# Crystal_Reset_Boot.net
KiCad netlist of a schematic drawn in Altium Designer
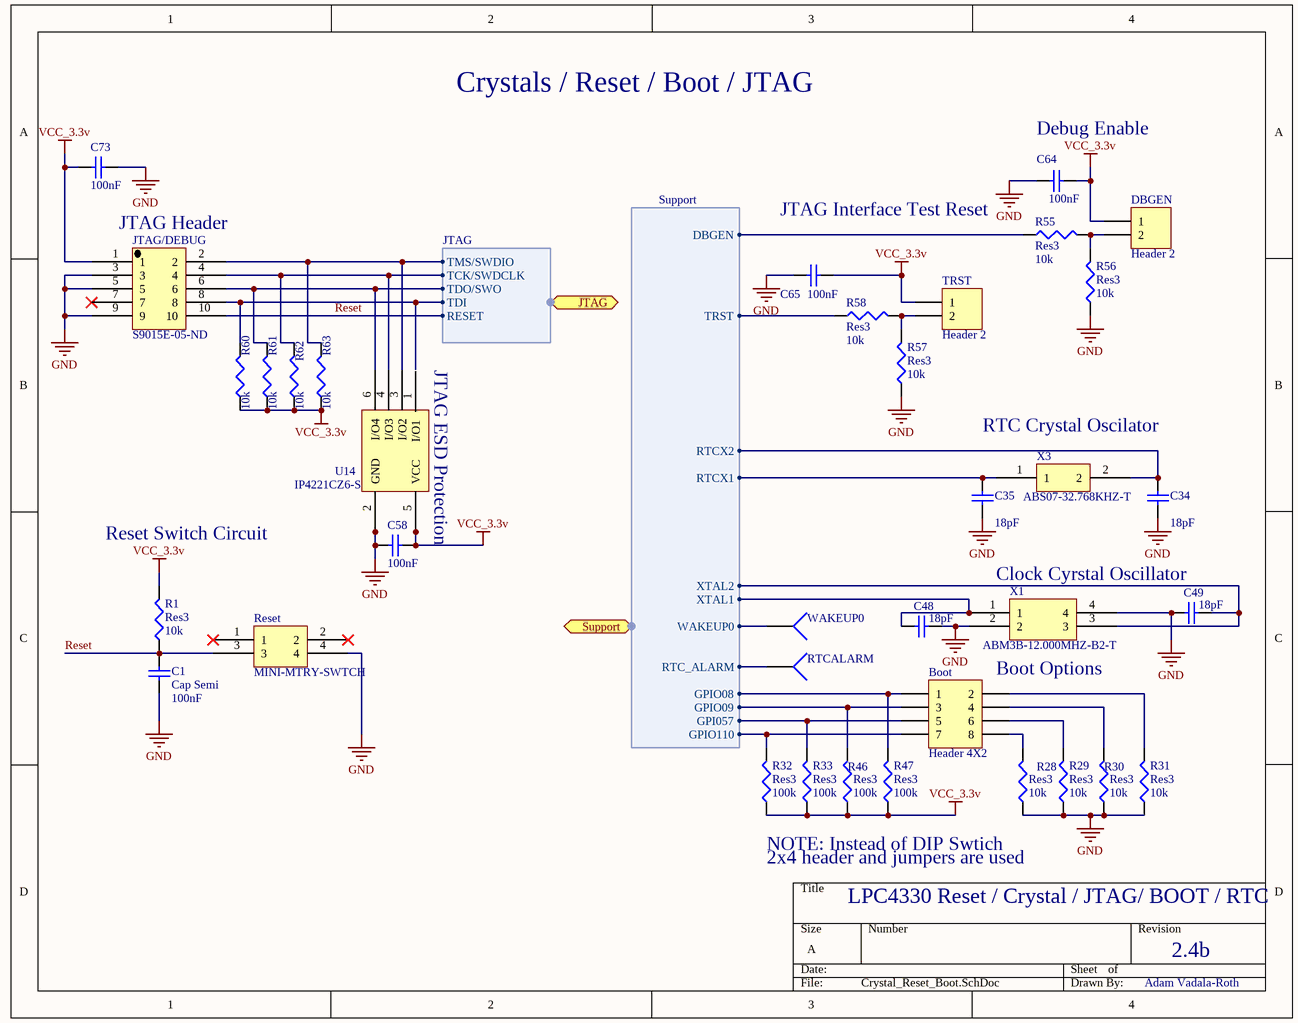
[diagram p0: Crystal_Reset_Boot.SchDoc]

(export (version "E")
  (design (tool "Eeschema 10.0.6"))
  (components
    (comp (ref "Boot")
      (value "Header 4X2")
      (footprint "HDR2X4")
      (description "Header, 4-Pin, Dual row")
      (fields (field (name "PUBLISHER") "Altium Limited"))
      (libsource (lib "Miscellaneous Connectors") (part "Header 4X2"))
    )
    (comp (ref "C1")
      (value "Cap Semi")
      (footprint "CAPC1608L")
      (description "Capacitor (Semiconductor SIM Model)")
      (fields (field (name "C1") "100nF") (field (name "PUBLISHER") "Altium Limited"))
      (libsource (lib "Miscellaneous Devices") (part "Cap Semi"))
    )
    (comp (ref "C34")
      (value "18pF")
      (footprint "1608[0603]")
      (description "Capacitor (Semiconductor SIM Model)")
      (fields (field (name "Comment") "Cap Semi") (field (name "PUBLISHER") "Altium Limited"))
      (libsource (lib "Miscellaneous Devices") (part "Cap Semi"))
    )
    (comp (ref "C35")
      (value "18pF")
      (footprint "1608[0603]")
      (description "Capacitor (Semiconductor SIM Model)")
      (fields (field (name "Comment") "Cap Semi") (field (name "PUBLISHER") "Altium Limited"))
      (libsource (lib "Miscellaneous Devices") (part "Cap Semi"))
    )
    (comp (ref "C48")
      (value "18pF")
      (footprint "1608[0603]")
      (description "Capacitor (Semiconductor SIM Model)")
      (fields (field (name "Comment") "Cap Semi") (field (name "PUBLISHER") "Altium Limited"))
      (libsource (lib "Miscellaneous Devices") (part "Cap Semi"))
    )
    (comp (ref "C49")
      (value "18pF")
      (footprint "1608[0603]")
      (description "Capacitor (Semiconductor SIM Model)")
      (fields (field (name "Comment") "Cap Semi") (field (name "PUBLISHER") "Altium Limited"))
      (libsource (lib "Miscellaneous Devices") (part "Cap Semi"))
    )
    (comp (ref "C58")
      (value "Cap Semi")
      (footprint "CAPC1608L")
      (description "Capacitor (Semiconductor SIM Model)")
      (fields (field (name "C1") "100nF") (field (name "PUBLISHER") "Altium Limited"))
      (libsource (lib "Miscellaneous Devices") (part "Cap Semi"))
    )
    (comp (ref "C64")
      (value "Cap Semi")
      (footprint "CAPC1608L")
      (description "Capacitor (Semiconductor SIM Model)")
      (fields (field (name "C1") "100nF") (field (name "PUBLISHER") "Altium Limited"))
      (libsource (lib "Miscellaneous Devices") (part "Cap Semi"))
    )
    (comp (ref "C65")
      (value "Cap Semi")
      (footprint "CAPC1608L")
      (description "Capacitor (Semiconductor SIM Model)")
      (fields (field (name "C1") "100nF") (field (name "PUBLISHER") "Altium Limited"))
      (libsource (lib "Miscellaneous Devices") (part "Cap Semi"))
    )
    (comp (ref "C73")
      (value "Cap Semi")
      (footprint "CAPC1608L")
      (description "Capacitor (Semiconductor SIM Model)")
      (fields (field (name "C1") "100nF") (field (name "PUBLISHER") "Altium Limited"))
      (libsource (lib "Miscellaneous Devices") (part "Cap Semi"))
    )
    (comp (ref "DBGEN")
      (value "Header 2")
      (footprint "HDR1X2")
      (description "Header, 2-Pin")
      (fields (field (name "PUBLISHER") "Altium Limited"))
      (libsource (lib "Miscellaneous Connectors") (part "Header 2"))
    )
    (comp (ref "JTAG/DEBUG")
      (value "S9015E-05-ND")
      (footprint "S9015E-05-ND")
      (libsource (lib "AHD Part Library") (part "S9015E-05-ND"))
    )
    (comp (ref "R1")
      (value "Res3")
      (footprint "J1-0603")
      (description "Resistor")
      (fields (field (name "ALTIUM_VALUE") "10k") (field (name "PUBLISHER") "Altium Limited"))
      (libsource (lib "Miscellaneous Devices") (part "Res3"))
    )
    (comp (ref "R28")
      (value "Res3")
      (footprint "J1-0603")
      (description "Resistor")
      (fields (field (name "ALTIUM_VALUE") "10k") (field (name "PUBLISHER") "Altium Limited"))
      (libsource (lib "Miscellaneous Devices") (part "Res3"))
    )
    (comp (ref "R29")
      (value "Res3")
      (footprint "J1-0603")
      (description "Resistor")
      (fields (field (name "ALTIUM_VALUE") "10k") (field (name "PUBLISHER") "Altium Limited"))
      (libsource (lib "Miscellaneous Devices") (part "Res3"))
    )
    (comp (ref "R30")
      (value "Res3")
      (footprint "J1-0603")
      (description "Resistor")
      (fields (field (name "ALTIUM_VALUE") "10k") (field (name "PUBLISHER") "Altium Limited"))
      (libsource (lib "Miscellaneous Devices") (part "Res3"))
    )
    (comp (ref "R31")
      (value "Res3")
      (footprint "J1-0603")
      (description "Resistor")
      (fields (field (name "ALTIUM_VALUE") "10k") (field (name "PUBLISHER") "Altium Limited"))
      (libsource (lib "Miscellaneous Devices") (part "Res3"))
    )
    (comp (ref "R32")
      (value "Res3")
      (footprint "J1-0603")
      (description "Resistor")
      (fields (field (name "ALTIUM_VALUE") "100k") (field (name "PUBLISHER") "Altium Limited"))
      (libsource (lib "Miscellaneous Devices") (part "Res3"))
    )
    (comp (ref "R33")
      (value "Res3")
      (footprint "J1-0603")
      (description "Resistor")
      (fields (field (name "ALTIUM_VALUE") "100k") (field (name "PUBLISHER") "Altium Limited"))
      (libsource (lib "Miscellaneous Devices") (part "Res3"))
    )
    (comp (ref "R46")
      (value "Res3")
      (footprint "J1-0603")
      (description "Resistor")
      (fields (field (name "ALTIUM_VALUE") "100k") (field (name "PUBLISHER") "Altium Limited"))
      (libsource (lib "Miscellaneous Devices") (part "Res3"))
    )
    (comp (ref "R47")
      (value "Res3")
      (footprint "J1-0603")
      (description "Resistor")
      (fields (field (name "ALTIUM_VALUE") "100k") (field (name "PUBLISHER") "Altium Limited"))
      (libsource (lib "Miscellaneous Devices") (part "Res3"))
    )
    (comp (ref "R55")
      (value "Res3")
      (footprint "J1-0603")
      (description "Resistor")
      (fields (field (name "ALTIUM_VALUE") "10k") (field (name "PUBLISHER") "Altium Limited"))
      (libsource (lib "Miscellaneous Devices") (part "Res3"))
    )
    (comp (ref "R56")
      (value "Res3")
      (footprint "J1-0603")
      (description "Resistor")
      (fields (field (name "ALTIUM_VALUE") "10k") (field (name "PUBLISHER") "Altium Limited"))
      (libsource (lib "Miscellaneous Devices") (part "Res3"))
    )
    (comp (ref "R57")
      (value "Res3")
      (footprint "J1-0603")
      (description "Resistor")
      (fields (field (name "ALTIUM_VALUE") "10k") (field (name "PUBLISHER") "Altium Limited"))
      (libsource (lib "Miscellaneous Devices") (part "Res3"))
    )
    (comp (ref "R58")
      (value "Res3")
      (footprint "J1-0603")
      (description "Resistor")
      (fields (field (name "ALTIUM_VALUE") "10k") (field (name "PUBLISHER") "Altium Limited"))
      (libsource (lib "Miscellaneous Devices") (part "Res3"))
    )
    (comp (ref "R60")
      (value "10k")
      (footprint "J1-0603")
      (description "Resistor")
      (fields (field (name "Comment") "Res3") (field (name "PUBLISHER") "Altium Limited"))
      (libsource (lib "Miscellaneous Devices") (part "Res3"))
    )
    (comp (ref "R61")
      (value "10k")
      (footprint "J1-0603")
      (description "Resistor")
      (fields (field (name "Comment") "Res3") (field (name "PUBLISHER") "Altium Limited"))
      (libsource (lib "Miscellaneous Devices") (part "Res3"))
    )
    (comp (ref "R62")
      (value "10k")
      (footprint "J1-0603")
      (description "Resistor")
      (fields (field (name "Comment") "Res3") (field (name "PUBLISHER") "Altium Limited"))
      (libsource (lib "Miscellaneous Devices") (part "Res3"))
    )
    (comp (ref "R63")
      (value "10k")
      (footprint "J1-0603")
      (description "Resistor")
      (fields (field (name "Comment") "Res3") (field (name "PUBLISHER") "Altium Limited"))
      (libsource (lib "Miscellaneous Devices") (part "Res3"))
    )
    (comp (ref "Reset")
      (value "MINI-MTRY-SWTCH")
      (footprint "Momentary Switch")
      (libsource (lib "AHD Part Library") (part "Mini Momemtary Switch"))
    )
    (comp (ref "RTCALARM")
      (value "Socket")
      (footprint "PIN1")
      (fields (field (name "PUBLISHER") "Altium Limited"))
      (libsource (lib "Miscellaneous Connectors") (part "Socket"))
    )
    (comp (ref "TRST")
      (value "Header 2")
      (footprint "HDR1X2")
      (description "Header, 2-Pin")
      (fields (field (name "PUBLISHER") "Altium Limited"))
      (libsource (lib "Miscellaneous Connectors") (part "Header 2"))
    )
    (comp (ref "U14")
      (value "IP4221CZ6-S")
      (footprint "IP4221CZ6-S")
      (libsource (lib "AHD Part Library") (part "IP4221CZ6-S"))
    )
    (comp (ref "WAKEUP0")
      (value "Socket")
      (footprint "PIN1")
      (fields (field (name "PUBLISHER") "Altium Limited"))
      (libsource (lib "Miscellaneous Connectors") (part "Socket"))
    )
    (comp (ref "X1")
      (value "ABM3B-12.000MHZ-B2-T")
      (footprint "ABM3B-12.000MHZ-B2-T")
      (libsource (lib "AHD Part Library") (part "ABM3B-12.000MHZ-B2-T"))
    )
    (comp (ref "X3")
      (value "ABS07-32.768KHZ-T")
      (footprint "ABS07-32.768KHZ-T")
      (description "ABS07-32.768KHZ-T RTC Crystal Oscillator")
      (libsource (lib "AHD Part Library") (part "ABS07-32.768KHZ-T"))
    )
  )
  (nets
    (net (code "3") (name "/DBGEN") (class "Default")
      (node (ref "R55") (pin "1") (pinfunction "1_1") (pintype "passive"))
    )
    (net (code "4") (name "/GPI057") (class "Default")
      (node (ref "Boot") (pin "5") (pinfunction "5_5") (pintype "passive"))
      (node (ref "R33") (pin "2") (pinfunction "2_2") (pintype "passive"))
    )
    (net (code "5") (name "/GPIO08") (class "Default")
      (node (ref "Boot") (pin "1") (pinfunction "1_1") (pintype "passive"))
      (node (ref "R47") (pin "2") (pinfunction "2_2") (pintype "passive"))
    )
    (net (code "6") (name "/GPIO09") (class "Default")
      (node (ref "Boot") (pin "3") (pinfunction "3_3") (pintype "passive"))
      (node (ref "R46") (pin "2") (pinfunction "2_2") (pintype "passive"))
    )
    (net (code "7") (name "/GPIO110") (class "Default")
      (node (ref "Boot") (pin "7") (pinfunction "7_7") (pintype "passive"))
      (node (ref "R32") (pin "2") (pinfunction "2_2") (pintype "passive"))
    )
    (net (code "8") (name "/RTCX1") (class "Default")
      (node (ref "C35") (pin "2") (pinfunction "2_2") (pintype "passive"))
      (node (ref "X3") (pin "1") (pinfunction "1_1") (pintype "passive"))
    )
    (net (code "9") (name "/RTCX2") (class "Default")
      (node (ref "C34") (pin "2") (pinfunction "2_2") (pintype "passive"))
      (node (ref "X3") (pin "2") (pinfunction "2_2") (pintype "passive"))
    )
    (net (code "10") (name "/RTC_ALARM") (class "Default")
      (node (ref "RTCALARM") (pin "1") (pinfunction "1_1") (pintype "passive"))
    )
    (net (code "11") (name "/Reset") (class "Default")
      (node (ref "C1") (pin "2") (pinfunction "2_2") (pintype "passive"))
      (node (ref "JTAG/DEBUG") (pin "10") (pinfunction "10_10") (pintype "passive"))
      (node (ref "R1") (pin "1") (pinfunction "1_1") (pintype "passive"))
      (node (ref "Reset") (pin "3") (pinfunction "3_3") (pintype "passive"))
    )
    (net (code "12") (name "/TCK{slash}SWDCLK") (class "Default")
      (node (ref "JTAG/DEBUG") (pin "4") (pinfunction "4_4") (pintype "passive"))
      (node (ref "R62") (pin "2") (pinfunction "2_2") (pintype "passive"))
      (node (ref "U14") (pin "4") (pinfunction "I/O3_4") (pintype "passive"))
    )
    (net (code "13") (name "/TDI") (class "Default")
      (node (ref "JTAG/DEBUG") (pin "8") (pinfunction "8_8") (pintype "passive"))
      (node (ref "R60") (pin "2") (pinfunction "2_2") (pintype "passive"))
    )
    (net (code "14") (name "/TDO{slash}SWO") (class "Default")
      (node (ref "JTAG/DEBUG") (pin "6") (pinfunction "6_6") (pintype "passive"))
      (node (ref "R61") (pin "2") (pinfunction "2_2") (pintype "passive"))
      (node (ref "U14") (pin "6") (pinfunction "I/O4_6") (pintype "passive"))
    )
    (net (code "15") (name "/TMS{slash}SWDIO") (class "Default")
      (node (ref "JTAG/DEBUG") (pin "2") (pinfunction "2_2") (pintype "passive"))
      (node (ref "R63") (pin "2") (pinfunction "2_2") (pintype "passive"))
      (node (ref "U14") (pin "3") (pinfunction "I/O2_3") (pintype "passive"))
    )
    (net (code "16") (name "/TRST") (class "Default")
      (node (ref "R58") (pin "1") (pinfunction "1_1") (pintype "passive"))
    )
    (net (code "17") (name "/WAKEUP0") (class "Default")
      (node (ref "WAKEUP0") (pin "1") (pinfunction "1_1") (pintype "passive"))
    )
    (net (code "18") (name "/XTAL1") (class "Default")
      (node (ref "C48") (pin "2") (pinfunction "2_2") (pintype "passive"))
      (node (ref "X1") (pin "1") (pinfunction "1_1") (pintype "passive"))
    )
    (net (code "19") (name "/XTAL2") (class "Default")
      (node (ref "C49") (pin "1") (pinfunction "1_1") (pintype "passive"))
      (node (ref "X1") (pin "3") (pinfunction "3_3") (pintype "passive"))
    )
    (net (code "22") (name "GND") (class "Default")
      (node (ref "C1") (pin "1") (pinfunction "1_1") (pintype "passive"))
      (node (ref "C34") (pin "1") (pinfunction "1_1") (pintype "passive"))
      (node (ref "C35") (pin "1") (pinfunction "1_1") (pintype "passive"))
      (node (ref "C48") (pin "1") (pinfunction "1_1") (pintype "passive"))
      (node (ref "C49") (pin "2") (pinfunction "2_2") (pintype "passive"))
      (node (ref "C58") (pin "1") (pinfunction "1_1") (pintype "passive"))
      (node (ref "C64") (pin "1") (pinfunction "1_1") (pintype "passive"))
      (node (ref "C65") (pin "1") (pinfunction "1_1") (pintype "passive"))
      (node (ref "C73") (pin "2") (pinfunction "2_2") (pintype "passive"))
      (node (ref "JTAG/DEBUG") (pin "3") (pinfunction "3_3") (pintype "passive"))
      (node (ref "JTAG/DEBUG") (pin "5") (pinfunction "5_5") (pintype "passive"))
      (node (ref "JTAG/DEBUG") (pin "9") (pinfunction "9_9") (pintype "passive"))
      (node (ref "R28") (pin "1") (pinfunction "1_1") (pintype "passive"))
      (node (ref "R29") (pin "1") (pinfunction "1_1") (pintype "passive"))
      (node (ref "R30") (pin "1") (pinfunction "1_1") (pintype "passive"))
      (node (ref "R31") (pin "1") (pinfunction "1_1") (pintype "passive"))
      (node (ref "R56") (pin "1") (pinfunction "1_1") (pintype "passive"))
      (node (ref "R57") (pin "1") (pinfunction "1_1") (pintype "passive"))
      (node (ref "Reset") (pin "4") (pinfunction "4_4") (pintype "passive"))
      (node (ref "U14") (pin "2") (pinfunction "GND_2") (pintype "passive"))
      (node (ref "X1") (pin "2") (pinfunction "2_2") (pintype "passive"))
      (node (ref "X1") (pin "4") (pinfunction "4_4") (pintype "passive"))
    )
    (net (code "23") (name "Net-(Boot-Pad2)") (class "Default")
      (node (ref "Boot") (pin "2") (pinfunction "2_2") (pintype "passive"))
      (node (ref "R31") (pin "2") (pinfunction "2_2") (pintype "passive"))
    )
    (net (code "24") (name "Net-(Boot-Pad4)") (class "Default")
      (node (ref "Boot") (pin "4") (pinfunction "4_4") (pintype "passive"))
      (node (ref "R30") (pin "2") (pinfunction "2_2") (pintype "passive"))
    )
    (net (code "25") (name "Net-(Boot-Pad6)") (class "Default")
      (node (ref "Boot") (pin "6") (pinfunction "6_6") (pintype "passive"))
      (node (ref "R29") (pin "2") (pinfunction "2_2") (pintype "passive"))
    )
    (net (code "26") (name "Net-(Boot-Pad8)") (class "Default")
      (node (ref "Boot") (pin "8") (pinfunction "8_8") (pintype "passive"))
      (node (ref "R28") (pin "2") (pinfunction "2_2") (pintype "passive"))
    )
    (net (code "27") (name "Net-(DBGEN-Pad2)") (class "Default")
      (node (ref "DBGEN") (pin "2") (pinfunction "2_2") (pintype "passive"))
      (node (ref "R55") (pin "2") (pinfunction "2_2") (pintype "passive"))
      (node (ref "R56") (pin "2") (pinfunction "2_2") (pintype "passive"))
    )
    (net (code "28") (name "Net-(R57-Pad2)") (class "Default")
      (node (ref "R57") (pin "2") (pinfunction "2_2") (pintype "passive"))
      (node (ref "R58") (pin "2") (pinfunction "2_2") (pintype "passive"))
      (node (ref "TRST") (pin "2") (pinfunction "2_2") (pintype "passive"))
    )
    (net (code "29") (name "VCC_3.3v") (class "Default")
      (node (ref "C58") (pin "2") (pinfunction "2_2") (pintype "passive"))
      (node (ref "C64") (pin "2") (pinfunction "2_2") (pintype "passive"))
      (node (ref "C65") (pin "2") (pinfunction "2_2") (pintype "passive"))
      (node (ref "C73") (pin "1") (pinfunction "1_1") (pintype "passive"))
      (node (ref "DBGEN") (pin "1") (pinfunction "1_1") (pintype "passive"))
      (node (ref "JTAG/DEBUG") (pin "1") (pinfunction "1_1") (pintype "passive"))
      (node (ref "R1") (pin "2") (pinfunction "2_2") (pintype "passive"))
      (node (ref "R32") (pin "1") (pinfunction "1_1") (pintype "passive"))
      (node (ref "R33") (pin "1") (pinfunction "1_1") (pintype "passive"))
      (node (ref "R46") (pin "1") (pinfunction "1_1") (pintype "passive"))
      (node (ref "R47") (pin "1") (pinfunction "1_1") (pintype "passive"))
      (node (ref "R60") (pin "1") (pinfunction "1_1") (pintype "passive"))
      (node (ref "R61") (pin "1") (pinfunction "1_1") (pintype "passive"))
      (node (ref "R62") (pin "1") (pinfunction "1_1") (pintype "passive"))
      (node (ref "R63") (pin "1") (pinfunction "1_1") (pintype "passive"))
      (node (ref "TRST") (pin "1") (pinfunction "1_1") (pintype "passive"))
      (node (ref "U14") (pin "5") (pinfunction "VCC_5") (pintype "passive"))
    )
    (net (code "30") (name "unconnected-(JTAG/DEBUG-Pad7)") (class "Default")
      (node (ref "JTAG/DEBUG") (pin "7") (pinfunction "7_7") (pintype "passive+no_connect"))
    )
    (net (code "31") (name "unconnected-(Reset-Pad1)") (class "Default")
      (node (ref "Reset") (pin "1") (pinfunction "1_1") (pintype "passive+no_connect"))
    )
    (net (code "32") (name "unconnected-(Reset-Pad2)") (class "Default")
      (node (ref "Reset") (pin "2") (pinfunction "2_2") (pintype "passive+no_connect"))
    )
    (net (code "33") (name "unconnected-(U14-I{slash}O1-Pad1)") (class "Default")
      (node (ref "U14") (pin "1") (pinfunction "I/O1_1") (pintype "passive"))
    )
  )
)
